# OSSI-1_COMMS_1.net
KiCad netlist of a schematic drawn in Altium Designer
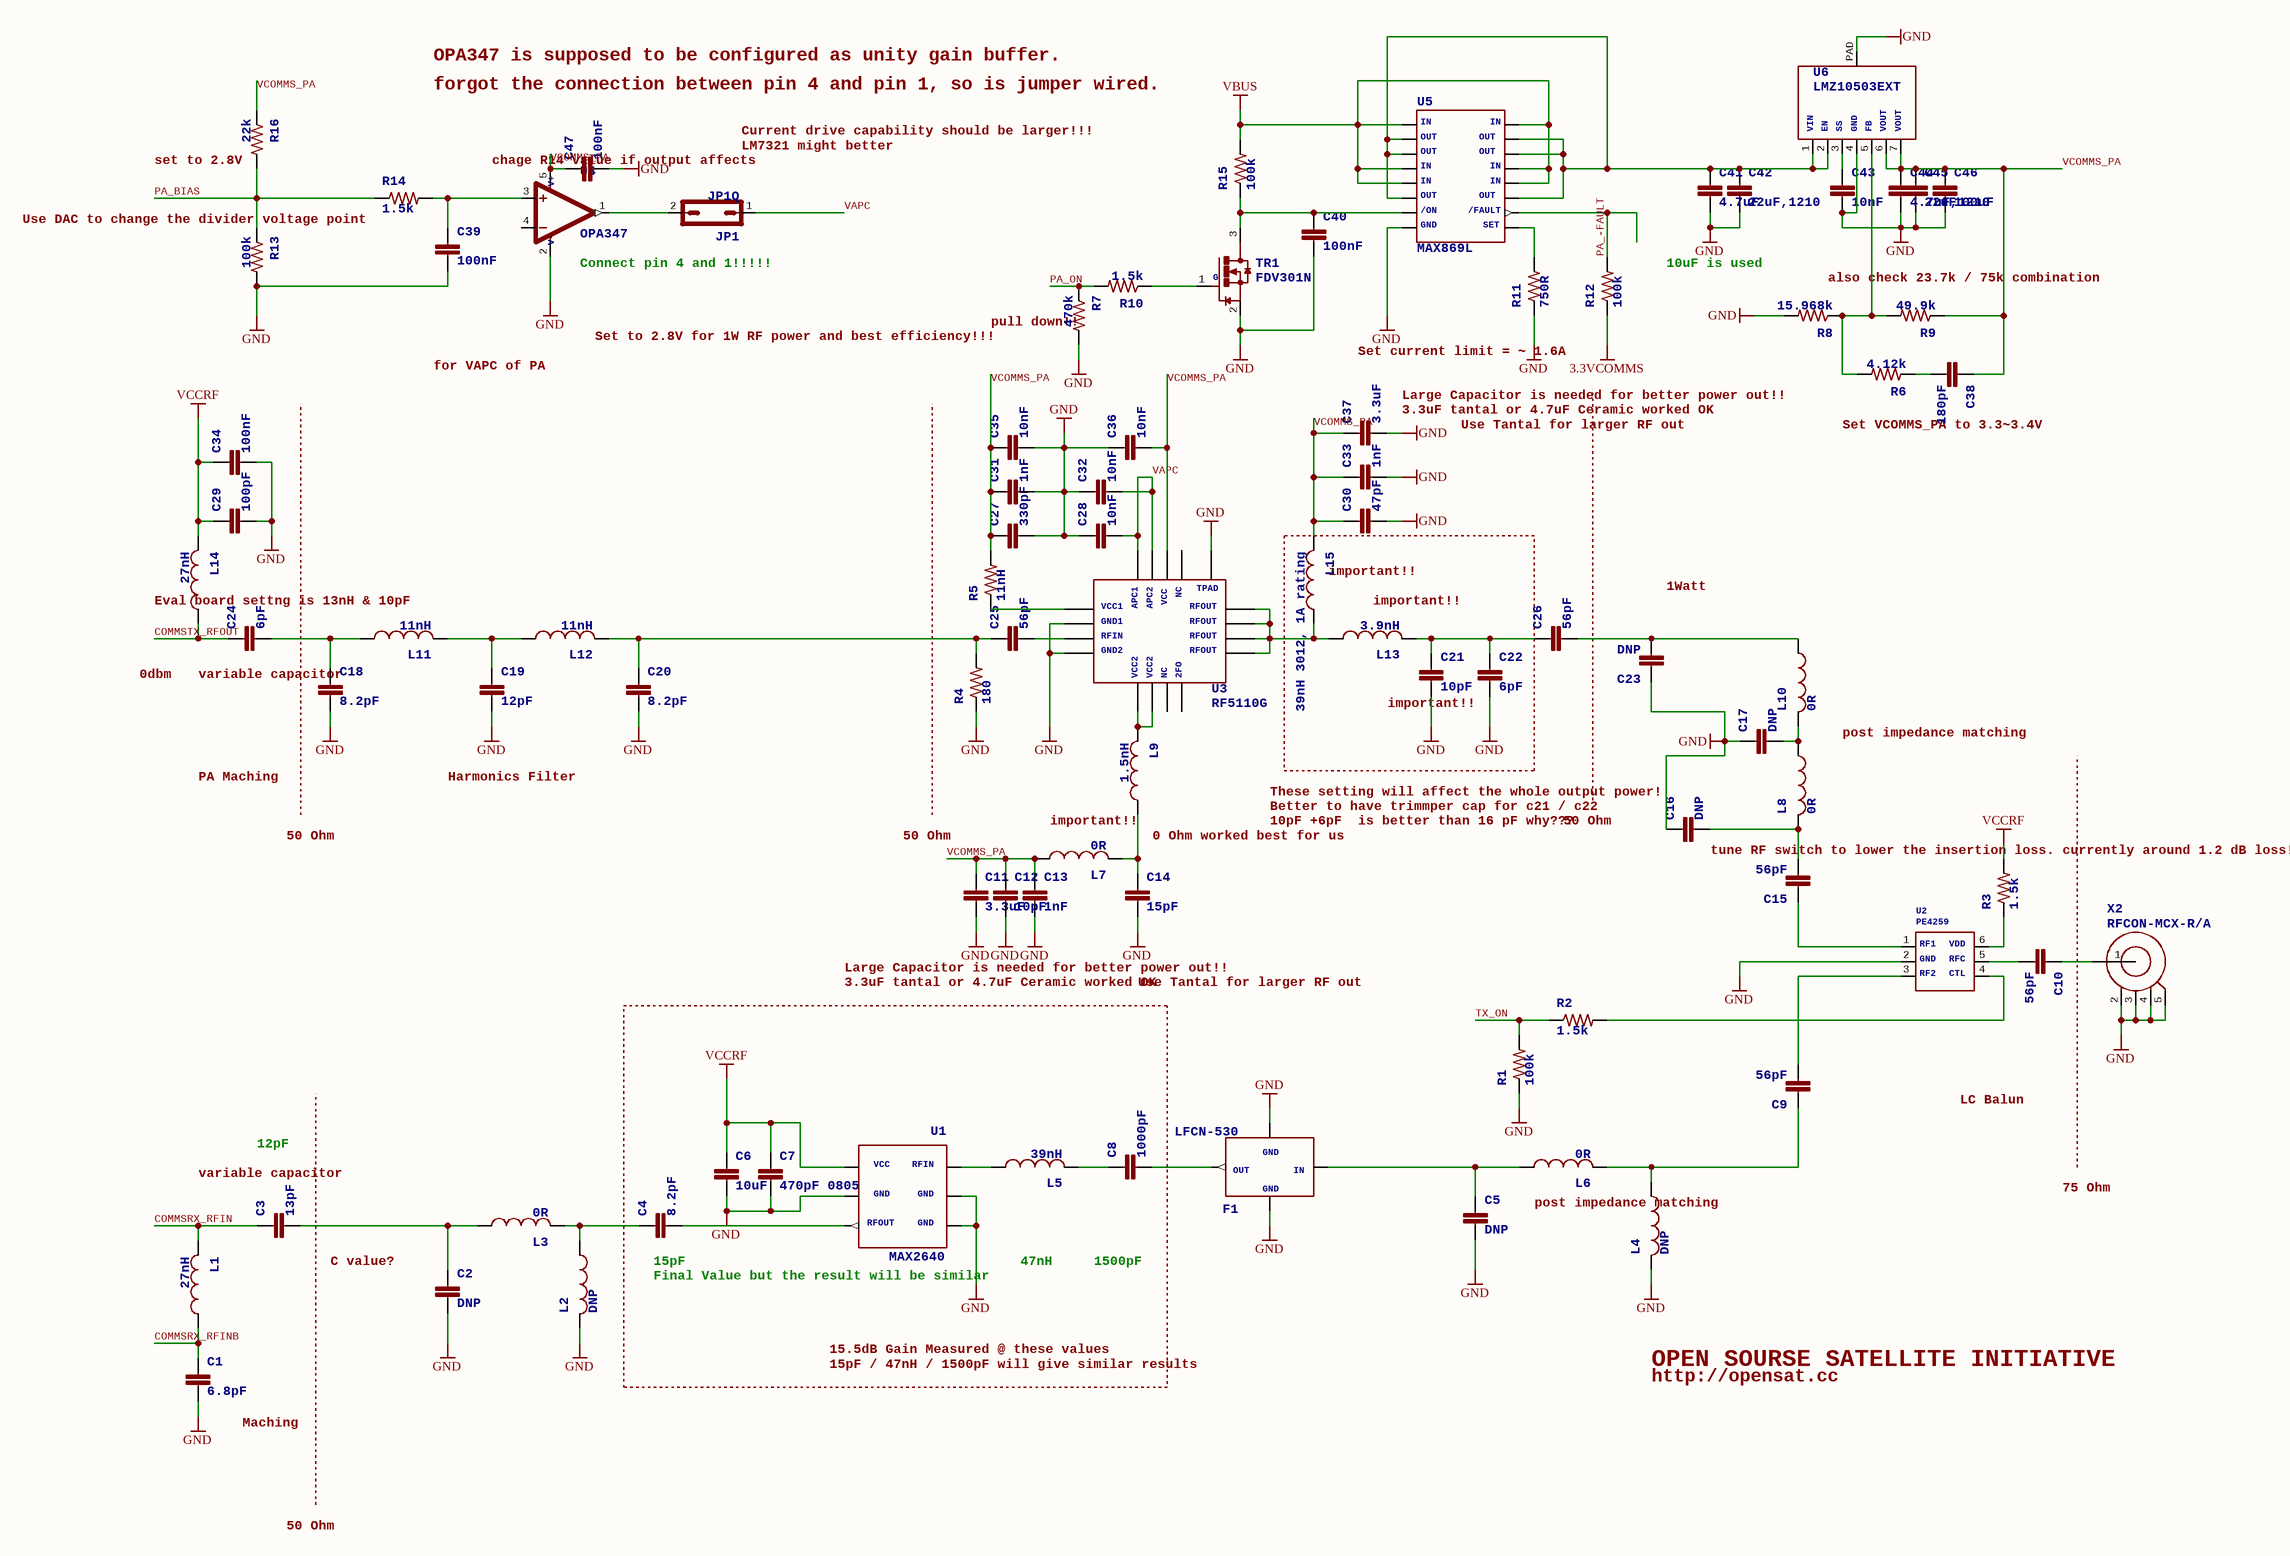
[diagram p0: OSSI-1 COMMS_1.SchDoc]

(export (version "E")
  (design (tool "Eeschema 10.0.6"))
  (components
    (comp (ref "C1")
      (value "6.8pF")
      (footprint "C0603(1608)")
      (fields (field (name ">NAME") "C1") (field (name ">VALUE") "6.8pF"))
      (libsource (lib "OSSI") (part "C0603(1608)"))
    )
    (comp (ref "C2")
      (value "DNP")
      (footprint "C0603(1608)")
      (fields (field (name ">NAME") "C2") (field (name ">VALUE") "DNP"))
      (libsource (lib "OSSI") (part "C0603(1608)"))
    )
    (comp (ref "C3")
      (value "13pF")
      (footprint "C0603(1608)")
      (fields (field (name ">NAME") "C3") (field (name ">VALUE") "13pF"))
      (libsource (lib "") (part "C0603(1608)_1"))
    )
    (comp (ref "C4")
      (value "8.2pF")
      (footprint "C0603(1608)")
      (fields (field (name ">NAME") "C4") (field (name ">VALUE") "8.2pF"))
      (libsource (lib "") (part "C0603(1608)_1"))
    )
    (comp (ref "C5")
      (value "DNP")
      (footprint "C0603(1608)")
      (fields (field (name ">NAME") "C5") (field (name ">VALUE") "DNP"))
      (libsource (lib "OSSI") (part "C0603(1608)"))
    )
    (comp (ref "C6")
      (value "10uF")
      (footprint "C1206-GCM31")
      (fields (field (name ">NAME") "C6") (field (name ">VALUE") "10uF"))
      (libsource (lib "OSSI") (part "C1206(3216)-GCM31"))
    )
    (comp (ref "C7")
      (value "470pF 0805")
      (footprint "C0805(2012)")
      (fields (field (name ">NAME") "C7") (field (name ">VALUE") "470pF 0805"))
      (libsource (lib "OSSI") (part "C0805(2012)"))
    )
    (comp (ref "C8")
      (value "1000pF")
      (footprint "C0603(1608)")
      (fields (field (name ">NAME") "C8") (field (name ">VALUE") "1000pF"))
      (libsource (lib "") (part "C0603(1608)_1"))
    )
    (comp (ref "C9")
      (value "56pF")
      (footprint "C0603(1608)")
      (fields (field (name ">NAME") "C9") (field (name ">VALUE") "56pF"))
      (libsource (lib "") (part "C0603(1608)_2"))
    )
    (comp (ref "C10")
      (value "56pF")
      (footprint "C0603(1608)")
      (fields (field (name ">NAME") "C10") (field (name ">VALUE") "56pF"))
      (libsource (lib "") (part "C0603(1608)_3"))
    )
    (comp (ref "C11")
      (value "3.3uF")
      (footprint "C1210-TMK325")
      (fields (field (name ">NAME") "C11") (field (name ">VALUE") "3.3uF"))
      (libsource (lib "OSSI") (part "C1210(3225)-TMK325"))
    )
    (comp (ref "C12")
      (value "10pF")
      (footprint "C0603(1608)")
      (fields (field (name ">NAME") "C12") (field (name ">VALUE") "10pF"))
      (libsource (lib "OSSI") (part "C0603(1608)"))
    )
    (comp (ref "C13")
      (value "1nF")
      (footprint "C0603(1608)")
      (fields (field (name ">NAME") "C13") (field (name ">VALUE") "1nF"))
      (libsource (lib "OSSI") (part "C0603(1608)"))
    )
    (comp (ref "C14")
      (value "15pF")
      (footprint "C0603(1608)")
      (fields (field (name ">NAME") "C14") (field (name ">VALUE") "15pF"))
      (libsource (lib "OSSI") (part "C0603(1608)"))
    )
    (comp (ref "C15")
      (value "56pF")
      (footprint "C0603(1608)")
      (fields (field (name ">NAME") "C15") (field (name ">VALUE") "56pF"))
      (libsource (lib "") (part "C0603(1608)_2"))
    )
    (comp (ref "C16")
      (value "DNP")
      (footprint "C0603(1608)")
      (fields (field (name ">NAME") "C16") (field (name ">VALUE") "DNP"))
      (libsource (lib "") (part "C0603(1608)_1"))
    )
    (comp (ref "C17")
      (value "DNP")
      (footprint "C0603(1608)")
      (fields (field (name ">NAME") "C17") (field (name ">VALUE") "DNP"))
      (libsource (lib "") (part "C0603(1608)_1"))
    )
    (comp (ref "C18")
      (value "8.2pF")
      (footprint "C0603(1608)")
      (fields (field (name ">NAME") "C18") (field (name ">VALUE") "8.2pF"))
      (libsource (lib "OSSI") (part "C0603(1608)"))
    )
    (comp (ref "C19")
      (value "12pF")
      (footprint "C0603(1608)")
      (fields (field (name ">NAME") "C19") (field (name ">VALUE") "12pF"))
      (libsource (lib "OSSI") (part "C0603(1608)"))
    )
    (comp (ref "C20")
      (value "8.2pF")
      (footprint "C0603(1608)")
      (fields (field (name ">NAME") "C20") (field (name ">VALUE") "8.2pF"))
      (libsource (lib "OSSI") (part "C0603(1608)"))
    )
    (comp (ref "C21")
      (value "10pF")
      (footprint "C0603(1608)")
      (fields (field (name ">NAME") "C21") (field (name ">VALUE") "10pF"))
      (libsource (lib "OSSI") (part "C0603(1608)"))
    )
    (comp (ref "C22")
      (value "6pF")
      (footprint "C0603(1608)")
      (fields (field (name ">NAME") "C22") (field (name ">VALUE") "6pF"))
      (libsource (lib "OSSI") (part "C0603(1608)"))
    )
    (comp (ref "C23")
      (value "DNP")
      (footprint "C0603(1608)")
      (fields (field (name ">NAME") "C23") (field (name ">VALUE") "DNP"))
      (libsource (lib "") (part "C0603(1608)_2"))
    )
    (comp (ref "C24")
      (value "6pF")
      (footprint "C0603(1608)")
      (fields (field (name ">NAME") "C24") (field (name ">VALUE") "6pF"))
      (libsource (lib "") (part "C0603(1608)_1"))
    )
    (comp (ref "C25")
      (value "56pF")
      (footprint "C0603(1608)")
      (fields (field (name ">NAME") "C25") (field (name ">VALUE") "56pF"))
      (libsource (lib "") (part "C0603(1608)_1"))
    )
    (comp (ref "C26")
      (value "56pF")
      (footprint "C0603(1608)")
      (fields (field (name ">NAME") "C26") (field (name ">VALUE") "56pF"))
      (libsource (lib "") (part "C0603(1608)_1"))
    )
    (comp (ref "C27")
      (value "330pF")
      (footprint "C0603(1608)")
      (fields (field (name ">NAME") "C27") (field (name ">VALUE") "330pF"))
      (libsource (lib "") (part "C0603(1608)_1"))
    )
    (comp (ref "C28")
      (value "10nF")
      (footprint "C0603(1608)")
      (fields (field (name ">NAME") "C28") (field (name ">VALUE") "10nF"))
      (libsource (lib "") (part "C0603(1608)_1"))
    )
    (comp (ref "C29")
      (value "100pF")
      (footprint "C0603(1608)")
      (fields (field (name ">NAME") "C29") (field (name ">VALUE") "100pF"))
      (libsource (lib "") (part "C0603(1608)_1"))
    )
    (comp (ref "C30")
      (value "47pF")
      (footprint "C0603(1608)")
      (fields (field (name ">NAME") "C30") (field (name ">VALUE") "47pF"))
      (libsource (lib "") (part "C0603(1608)_1"))
    )
    (comp (ref "C31")
      (value "1nF")
      (footprint "C0603(1608)")
      (fields (field (name ">NAME") "C31") (field (name ">VALUE") "1nF"))
      (libsource (lib "") (part "C0603(1608)_1"))
    )
    (comp (ref "C32")
      (value "10nF")
      (footprint "C0603(1608)")
      (fields (field (name ">NAME") "C32") (field (name ">VALUE") "10nF"))
      (libsource (lib "") (part "C0603(1608)_1"))
    )
    (comp (ref "C33")
      (value "1nF")
      (footprint "C0603(1608)")
      (fields (field (name ">NAME") "C33") (field (name ">VALUE") "1nF"))
      (libsource (lib "") (part "C0603(1608)_1"))
    )
    (comp (ref "C34")
      (value "100nF")
      (footprint "C0603(1608)")
      (fields (field (name ">NAME") "C34") (field (name ">VALUE") "100nF"))
      (libsource (lib "") (part "C0603(1608)_1"))
    )
    (comp (ref "C35")
      (value "10nF")
      (footprint "C0603(1608)")
      (fields (field (name ">NAME") "C35") (field (name ">VALUE") "10nF"))
      (libsource (lib "") (part "C0603(1608)_1"))
    )
    (comp (ref "C36")
      (value "10nF")
      (footprint "C0603(1608)")
      (fields (field (name ">NAME") "C36") (field (name ">VALUE") "10nF"))
      (libsource (lib "") (part "C0603(1608)_1"))
    )
    (comp (ref "C37")
      (value "3.3uF")
      (footprint "C1210-TMK325")
      (fields (field (name ">NAME") "C37") (field (name ">VALUE") "3.3uF"))
      (libsource (lib "") (part "C1210(3225)-TMK325_1"))
    )
    (comp (ref "C38")
      (value "180pF")
      (footprint "C0603(1608)")
      (fields (field (name ">NAME") "C38") (field (name ">VALUE") "180pF"))
      (libsource (lib "") (part "C0603(1608)_3"))
    )
    (comp (ref "C39")
      (value "100nF")
      (footprint "C0603(1608)")
      (fields (field (name ">NAME") "C39") (field (name ">VALUE") "100nF"))
      (libsource (lib "OSSI") (part "C0603(1608)"))
    )
    (comp (ref "C40")
      (value "100nF")
      (footprint "C0603(1608)")
      (fields (field (name ">NAME") "C40") (field (name ">VALUE") "100nF"))
      (libsource (lib "OSSI") (part "C0603(1608)"))
    )
    (comp (ref "C41")
      (value "4.7uF")
      (footprint "C1210-GCM32")
      (fields (field (name ">NAME") "C41") (field (name ">VALUE") "4.7uF"))
      (libsource (lib "OSSI") (part "C1210(3225)-GCM32"))
    )
    (comp (ref "C42")
      (value "22uF,1210")
      (footprint "C1210-GCM32")
      (fields (field (name ">NAME") "C42") (field (name ">VALUE") "22uF,1210"))
      (libsource (lib "OSSI") (part "C1210(3225)-GCM32"))
    )
    (comp (ref "C43")
      (value "10nF")
      (footprint "C0603(1608)")
      (fields (field (name ">NAME") "C43") (field (name ">VALUE") "10nF"))
      (libsource (lib "OSSI") (part "C0603(1608)"))
    )
    (comp (ref "C44")
      (value "4.7uF,1210")
      (footprint "C0805(2012)")
      (fields (field (name ">NAME") "C44") (field (name ">VALUE") "4.7uF,1210"))
      (libsource (lib "OSSI") (part "C0805(2012)"))
    )
    (comp (ref "C45")
      (value "22uF")
      (footprint "C1210-GCM32")
      (fields (field (name ">NAME") "C45") (field (name ">VALUE") "22uF"))
      (libsource (lib "OSSI") (part "C1210(3225)-GCM32"))
    )
    (comp (ref "C46")
      (value "100uF")
      (footprint "C1210-GCM32")
      (fields (field (name ">NAME") "C46") (field (name ">VALUE") "100uF"))
      (libsource (lib "OSSI") (part "C1210(3225)-GCM32"))
    )
    (comp (ref "C47")
      (value "100nF")
      (footprint "C0603(1608)")
      (fields (field (name ">NAME") "C47") (field (name ">VALUE") "100nF"))
      (libsource (lib "") (part "C0603(1608)_1"))
    )
    (comp (ref "F1")
      (value "LFCN-530")
      (footprint "LFCN")
      (fields
        (field (name "IN") "IN")
        (field (name "OUT") "OUT")
        (field (name "GND") "GND")
        (field (name "GND_1") "GND")
        (field (name ">NAME") "F1")
        (field (name ">VALUE") "LFCN-530")
      )
      (libsource (lib "OSSI") (part "LFCN-160"))
    )
    (comp (ref "JP1")
      (value "JP1Q")
      (footprint "JP1")
      (description "<b>JUMPER</b>")
      (fields (field (name ">NAME") "JP1") (field (name ">VALUE") "JP1Q"))
      (libsource (lib "OSSI") (part "JP1Q"))
    )
    (comp (ref "L1")
      (value "27nH")
      (footprint "L0603(1608)")
      (fields (field (name ">NAME") "L1") (field (name ">VALUE") "27nH"))
      (libsource (lib "OSSI") (part "L0603(1608)"))
    )
    (comp (ref "L2")
      (value "DNP")
      (footprint "L0603(1608)")
      (fields (field (name ">NAME") "L2") (field (name ">VALUE") "DNP"))
      (libsource (lib "OSSI") (part "L0603(1608)"))
    )
    (comp (ref "L3")
      (value "0R")
      (footprint "L0603(1608)")
      (fields (field (name ">NAME") "L3") (field (name ">VALUE") "0R"))
      (libsource (lib "OSSI") (part "L0603(1608)"))
    )
    (comp (ref "L4")
      (value "DNP")
      (footprint "L0603(1608)")
      (fields (field (name ">NAME") "L4") (field (name ">VALUE") "DNP"))
      (libsource (lib "OSSI") (part "L0603(1608)"))
    )
    (comp (ref "L5")
      (value "39nH")
      (footprint "L0603(1608)")
      (fields (field (name ">NAME") "L5") (field (name ">VALUE") "39nH"))
      (libsource (lib "OSSI") (part "L0603(1608)"))
    )
    (comp (ref "L6")
      (value "0R")
      (footprint "L0603(1608)")
      (fields (field (name ">NAME") "L6") (field (name ">VALUE") "0R"))
      (libsource (lib "OSSI") (part "L0603(1608)"))
    )
    (comp (ref "L7")
      (value "0R")
      (footprint "LQH32CN331K23L")
      (fields (field (name ">NAME") "L7") (field (name ">VALUE") "0R"))
      (libsource (lib "OSSI") (part "LLQH32CN"))
    )
    (comp (ref "L8")
      (value "0R")
      (footprint "L0603(1608)")
      (fields (field (name ">NAME") "L8") (field (name ">VALUE") "0R"))
      (libsource (lib "OSSI") (part "L0603(1608)"))
    )
    (comp (ref "L9")
      (value "1.5nH")
      (footprint "L0603(1608)")
      (fields (field (name ">NAME") "L9") (field (name ">VALUE") "1.5nH"))
      (libsource (lib "OSSI") (part "L0603(1608)"))
    )
    (comp (ref "L10")
      (value "0R")
      (footprint "L0603(1608)")
      (fields (field (name ">NAME") "L10") (field (name ">VALUE") "0R"))
      (libsource (lib "OSSI") (part "L0603(1608)"))
    )
    (comp (ref "L11")
      (value "11nH")
      (footprint "L0603(1608)")
      (fields (field (name ">NAME") "L11") (field (name ">VALUE") "11nH"))
      (libsource (lib "OSSI") (part "L0603(1608)"))
    )
    (comp (ref "L12")
      (value "11nH")
      (footprint "L0603(1608)")
      (fields (field (name ">NAME") "L12") (field (name ">VALUE") "11nH"))
      (libsource (lib "OSSI") (part "L0603(1608)"))
    )
    (comp (ref "L13")
      (value "3.9nH")
      (footprint "L0603(1608)")
      (fields (field (name ">NAME") "L13") (field (name ">VALUE") "3.9nH"))
      (libsource (lib "OSSI") (part "L0603(1608)"))
    )
    (comp (ref "L14")
      (value "27nH")
      (footprint "L0603(1608)")
      (fields (field (name ">NAME") "L14") (field (name ">VALUE") "27nH"))
      (libsource (lib "OSSI") (part "L0603(1608)"))
    )
    (comp (ref "L15")
      (value "39nH 3012, 1A rating")
      (footprint "NR3012")
      (fields (field (name ">NAME") "L15") (field (name ">VALUE") "39nH 3012, 1A rating"))
      (libsource (lib "OSSI") (part "LNR3012"))
    )
    (comp (ref "R1")
      (value "100k")
      (footprint "R0603(1608)")
      (fields (field (name ">NAME") "R1") (field (name ">VALUE") "100k"))
      (libsource (lib "OSSI") (part "R0603(1608)"))
    )
    (comp (ref "R2")
      (value "1.5k")
      (footprint "R0603(1608)")
      (fields (field (name ">NAME") "R2") (field (name ">VALUE") "1.5k"))
      (libsource (lib "OSSI") (part "R0603(1608)"))
    )
    (comp (ref "R3")
      (value "1.5k")
      (footprint "R0603(1608)")
      (fields (field (name ">NAME") "R3") (field (name ">VALUE") "1.5k"))
      (libsource (lib "OSSI") (part "R0603(1608)"))
    )
    (comp (ref "R4")
      (value "180")
      (footprint "R0603(1608)")
      (fields (field (name ">NAME") "R4") (field (name ">VALUE") "180"))
      (libsource (lib "OSSI") (part "R0603(1608)"))
    )
    (comp (ref "R5")
      (value "11nH")
      (footprint "R0603(1608)")
      (fields (field (name ">NAME") "R5") (field (name ">VALUE") "11nH"))
      (libsource (lib "OSSI") (part "R0603(1608)"))
    )
    (comp (ref "R6")
      (value "4.12k")
      (footprint "R0603(1608)")
      (fields (field (name ">NAME") "R6") (field (name ">VALUE") "4.12k"))
      (libsource (lib "OSSI") (part "R0603(1608)"))
    )
    (comp (ref "R7")
      (value "470k")
      (footprint "R0603(1608)")
      (fields (field (name ">NAME") "R7") (field (name ">VALUE") "470k"))
      (libsource (lib "OSSI") (part "R0603(1608)"))
    )
    (comp (ref "R8")
      (value "15.968k")
      (footprint "R0603(1608)")
      (fields (field (name ">NAME") "R8") (field (name ">VALUE") "15.968k"))
      (libsource (lib "OSSI") (part "R0603(1608)"))
    )
    (comp (ref "R9")
      (value "49.9k")
      (footprint "R0603(1608)")
      (fields (field (name ">NAME") "R9") (field (name ">VALUE") "49.9k"))
      (libsource (lib "OSSI") (part "R0603(1608)"))
    )
    (comp (ref "R10")
      (value "1.5k")
      (footprint "R0603(1608)")
      (fields (field (name ">NAME") "R10") (field (name ">VALUE") "1.5k"))
      (libsource (lib "OSSI") (part "R0603(1608)"))
    )
    (comp (ref "R11")
      (value "750R")
      (footprint "R0603(1608)")
      (fields (field (name ">NAME") "R11") (field (name ">VALUE") "750R"))
      (libsource (lib "OSSI") (part "R0603(1608)"))
    )
    (comp (ref "R12")
      (value "100k")
      (footprint "R0603(1608)")
      (fields (field (name ">NAME") "R12") (field (name ">VALUE") "100k"))
      (libsource (lib "OSSI") (part "R0603(1608)"))
    )
    (comp (ref "R13")
      (value "100k")
      (footprint "R0603(1608)")
      (fields (field (name ">NAME") "R13") (field (name ">VALUE") "100k"))
      (libsource (lib "OSSI") (part "R0603(1608)"))
    )
    (comp (ref "R14")
      (value "1.5k")
      (footprint "R0603(1608)")
      (fields (field (name ">NAME") "R14") (field (name ">VALUE") "1.5k"))
      (libsource (lib "OSSI") (part "R0603(1608)"))
    )
    (comp (ref "R15")
      (value "100k")
      (footprint "R0603(1608)")
      (fields (field (name ">NAME") "R15") (field (name ">VALUE") "100k"))
      (libsource (lib "OSSI") (part "R0603(1608)"))
    )
    (comp (ref "R16")
      (value "22k")
      (footprint "R0603(1608)")
      (fields (field (name ">NAME") "R16") (field (name ">VALUE") "22k"))
      (libsource (lib "OSSI") (part "R0603(1608)"))
    )
    (comp (ref "TR1")
      (value "FDV301N")
      (footprint "SOT23")
      (description "FDV301N Digital N channel - FET / Rdson = 5 Ohm / Vgs = 0.7~1.06V / Ids = 220mA")
      (fields (field (name "G") "G") (field (name ">NAME") "TR1") (field (name ">VALUE") "FDV301N"))
      (libsource (lib "OSSI") (part "FDV301N"))
    )
    (comp (ref "U1")
      (value "MAX2640")
      (footprint "SOT23-6")
      (fields
        (field (name ">NAME") "U1")
        (field (name "RFIN") "RFIN")
        (field (name "GND") "GND")
        (field (name "GND_1") "GND")
        (field (name "RFOUT") "RFOUT")
        (field (name "GND_2") "GND")
        (field (name "VCC") "VCC")
        (field (name ">VALUE") "MAX2640")
      )
      (libsource (lib "OSSI") (part "MAX2640"))
    )
    (comp (ref "U2")
      (value "PE4259")
      (footprint "SC70-6")
      (fields
        (field (name "RF1") "RF1")
        (field (name "GND") "GND")
        (field (name "RF2") "RF2")
        (field (name "CTL") "CTL")
        (field (name "RFC") "RFC")
        (field (name "VDD") "VDD")
        (field (name ">NAME") "U2")
        (field (name ">VALUE") "PE4259")
      )
      (libsource (lib "OSSI") (part "PE4259"))
    )
    (comp (ref "U3")
      (value "RF5110G")
      (footprint "RF5110G")
      (description "<b>RF5110G</b>\n<br />\n3V GSM RF Power Amplifirer\n<br />\n+36dBm Output Power at 3.5V")
      (fields
        (field (name "VCC1") "VCC1")
        (field (name "GND1") "GND1")
        (field (name "RFIN") "RFIN")
        (field (name "GND2") "GND2")
        (field (name "VCC2") "VCC2")
        (field (name "VCC2_1") "VCC2")
        (field (name "NC") "NC")
        (field (name "2FO") "2FO")
        (field (name "RFOUT") "RFOUT")
        (field (name "RFOUT_1") "RFOUT")
        (field (name "RFOUT_2") "RFOUT")
        (field (name "RFOUT_3") "RFOUT")
        (field (name "NC_1") "NC")
        (field (name "VCC") "VCC")
        (field (name "APC2") "APC2")
        (field (name "APC1") "APC1")
        (field (name ">NAME") "U3")
        (field (name ">VALUE") "RF5110G")
        (field (name "TPAD") "TPAD")
      )
      (libsource (lib "OSSI") (part "RF5110G"))
    )
    (comp (ref "U4")
      (value "OPA347")
      (footprint "SOT23-5DBV")
      (fields
        (field (name ">NAME") "U4")
        (field (name ">VALUE") "OPA347")
        (field (name "V+") "V+")
        (field (name "V-") "V-")
      )
      (libsource (lib "OSSI") (part "OPA347"))
    )
    (comp (ref "U5")
      (value "MAX869L")
      (footprint "16QSOP")
      (description "2A, Current-Limited, High-Side\nP-Channel Switch with Thermal Shutdown")
      (fields
        (field (name "IN") "IN")
        (field (name "OUT") "OUT")
        (field (name "OUT_1") "OUT")
        (field (name "IN_1") "IN")
        (field (name "IN_2") "IN")
        (field (name "IN_3") "IN")
        (field (name "IN_4") "IN")
        (field (name "IN_5") "IN")
        (field (name "OUT_2") "OUT")
        (field (name "GND") "GND")
        (field (name "OUT_3") "OUT")
        (field (name "OUT_4") "OUT")
        (field (name "OUT_5") "OUT")
        (field (name "/ON") "/ON")
        (field (name "/FAULT") "/FAULT")
        (field (name "SET") "SET")
        (field (name ">NAME") "U5")
        (field (name ">VALUE") "MAX869L")
      )
      (libsource (lib "OSSI") (part "MAX869L"))
    )
    (comp (ref "U6")
      (value "LMZ10503EXT")
      (footprint "TO-PMOD-7")
      (fields
        (field (name "VIN") "VIN")
        (field (name "EN") "EN")
        (field (name "SS") "SS")
        (field (name "GND") "GND")
        (field (name "FB") "FB")
        (field (name "VOUT") "VOUT")
        (field (name "VOUT_1") "VOUT")
        (field (name ">NAME") "U6")
        (field (name ">VALUE") "LMZ10503EXT")
      )
      (libsource (lib "OSSI") (part "LMZ10503EXT"))
    )
    (comp (ref "X2")
      (value "RFCON-MCX-R/A")
      (footprint "MCX-R/A")
      (description "RF Connectors")
      (fields (field (name ">NAME") "X2") (field (name ">VALUE") "RFCON-MCX-R/A"))
      (libsource (lib "OSSI") (part "RFCON-MCX-R/A"))
    )
  )
  (nets
    (net (code "1") (name "/COMMSRX_RFIN") (class "Default")
      (node (ref "C3") (pin "1") (pinfunction "1_1") (pintype "passive"))
      (node (ref "L1") (pin "2") (pinfunction "2_2") (pintype "passive"))
    )
    (net (code "2") (name "/COMMSRX_RFINB") (class "Default")
      (node (ref "C1") (pin "1") (pinfunction "1_1") (pintype "passive"))
      (node (ref "L1") (pin "1") (pinfunction "1_1") (pintype "passive"))
    )
    (net (code "3") (name "/COMMSTX_RFOUT") (class "Default")
      (node (ref "C24") (pin "1") (pinfunction "1_1") (pintype "passive"))
      (node (ref "L14") (pin "1") (pinfunction "1_1") (pintype "passive"))
    )
    (net (code "4") (name "/PA_-FAULT") (class "Default")
      (node (ref "R12") (pin "2") (pinfunction "2_2") (pintype "passive"))
      (node (ref "U5") (pin "10") (pinfunction "P$10_10") (pintype "output"))
    )
    (net (code "5") (name "/PA_BIAS") (class "Default")
      (node (ref "R13") (pin "1") (pinfunction "1_1") (pintype "passive"))
      (node (ref "R14") (pin "1") (pinfunction "1_1") (pintype "passive"))
      (node (ref "R16") (pin "2") (pinfunction "2_2") (pintype "passive"))
    )
    (net (code "6") (name "/PA_ON") (class "Default")
      (node (ref "R10") (pin "2") (pinfunction "2_2") (pintype "passive"))
      (node (ref "R7") (pin "1") (pinfunction "1_1") (pintype "passive"))
    )
    (net (code "7") (name "/TX_ON") (class "Default")
      (node (ref "R1") (pin "2") (pinfunction "2_2") (pintype "passive"))
      (node (ref "R2") (pin "1") (pinfunction "1_1") (pintype "passive"))
    )
    (net (code "8") (name "/VAPC") (class "Default")
      (node (ref "C28") (pin "2") (pinfunction "2_2") (pintype "passive"))
      (node (ref "C32") (pin "2") (pinfunction "2_2") (pintype "passive"))
      (node (ref "JP1") (pin "1") (pinfunction "1_1") (pintype "passive"))
      (node (ref "U3") (pin "15") (pinfunction "P$15_15") (pintype "passive"))
      (node (ref "U3") (pin "16") (pinfunction "P$16_16") (pintype "passive"))
    )
    (net (code "9") (name "/VCOMMS_PA") (class "Default")
      (node (ref "C11") (pin "P$1") (pinfunction "1_P$1") (pintype "passive"))
      (node (ref "C12") (pin "1") (pinfunction "1_1") (pintype "passive"))
      (node (ref "C13") (pin "1") (pinfunction "1_1") (pintype "passive"))
      (node (ref "C27") (pin "1") (pinfunction "1_1") (pintype "passive"))
      (node (ref "C30") (pin "1") (pinfunction "1_1") (pintype "passive"))
      (node (ref "C31") (pin "1") (pinfunction "1_1") (pintype "passive"))
      (node (ref "C33") (pin "1") (pinfunction "1_1") (pintype "passive"))
      (node (ref "C35") (pin "1") (pinfunction "1_1") (pintype "passive"))
      (node (ref "C36") (pin "2") (pinfunction "2_2") (pintype "passive"))
      (node (ref "C37") (pin "P$1") (pinfunction "1_P$1") (pintype "passive"))
      (node (ref "C38") (pin "1") (pinfunction "1_1") (pintype "passive"))
      (node (ref "C44") (pin "1") (pinfunction "1_1") (pintype "passive"))
      (node (ref "C45") (pin "P$1") (pinfunction "1_P$1") (pintype "passive"))
      (node (ref "C46") (pin "P$1") (pinfunction "1_P$1") (pintype "passive"))
      (node (ref "C47") (pin "1") (pinfunction "1_1") (pintype "passive"))
      (node (ref "L15") (pin "P$2") (pinfunction "2_P$2") (pintype "passive"))
      (node (ref "L7") (pin "P$1") (pinfunction "1_P$1") (pintype "passive"))
      (node (ref "R16") (pin "1") (pinfunction "1_1") (pintype "passive"))
      (node (ref "R5") (pin "2") (pinfunction "2_2") (pintype "passive"))
      (node (ref "R9") (pin "1") (pinfunction "1_1") (pintype "passive"))
      (node (ref "U3") (pin "14") (pinfunction "P$14_14") (pintype "passive"))
      (node (ref "U4") (pin "5") (pinfunction "V+_5") (pintype "power_in"))
      (node (ref "U6") (pin "6") (pinfunction "P$6_6") (pintype "power_in"))
      (node (ref "U6") (pin "7") (pinfunction "P$7_7") (pintype "power_in"))
    )
    (net (code "10") (name "3.3VCOMMS") (class "Default")
      (node (ref "R12") (pin "1") (pinfunction "1_1") (pintype "passive"))
    )
    (net (code "11") (name "GND") (class "Default")
      (node (ref "C1") (pin "2") (pinfunction "2_2") (pintype "passive"))
      (node (ref "C11") (pin "P$2") (pinfunction "2_P$2") (pintype "passive"))
      (node (ref "C12") (pin "2") (pinfunction "2_2") (pintype "passive"))
      (node (ref "C13") (pin "2") (pinfunction "2_2") (pintype "passive"))
      (node (ref "C14") (pin "2") (pinfunction "2_2") (pintype "passive"))
      (node (ref "C16") (pin "1") (pinfunction "1_1") (pintype "passive"))
      (node (ref "C17") (pin "1") (pinfunction "1_1") (pintype "passive"))
      (node (ref "C18") (pin "2") (pinfunction "2_2") (pintype "passive"))
      (node (ref "C19") (pin "2") (pinfunction "2_2") (pintype "passive"))
      (node (ref "C2") (pin "2") (pinfunction "2_2") (pintype "passive"))
      (node (ref "C20") (pin "2") (pinfunction "2_2") (pintype "passive"))
      (node (ref "C21") (pin "2") (pinfunction "2_2") (pintype "passive"))
      (node (ref "C22") (pin "2") (pinfunction "2_2") (pintype "passive"))
      (node (ref "C23") (pin "1") (pinfunction "1_1") (pintype "passive"))
      (node (ref "C27") (pin "2") (pinfunction "2_2") (pintype "passive"))
      (node (ref "C28") (pin "1") (pinfunction "1_1") (pintype "passive"))
      (node (ref "C29") (pin "2") (pinfunction "2_2") (pintype "passive"))
      (node (ref "C30") (pin "2") (pinfunction "2_2") (pintype "passive"))
      (node (ref "C31") (pin "2") (pinfunction "2_2") (pintype "passive"))
      (node (ref "C32") (pin "1") (pinfunction "1_1") (pintype "passive"))
      (node (ref "C33") (pin "2") (pinfunction "2_2") (pintype "passive"))
      (node (ref "C34") (pin "2") (pinfunction "2_2") (pintype "passive"))
      (node (ref "C35") (pin "2") (pinfunction "2_2") (pintype "passive"))
      (node (ref "C36") (pin "1") (pinfunction "1_1") (pintype "passive"))
      (node (ref "C37") (pin "P$2") (pinfunction "2_P$2") (pintype "passive"))
      (node (ref "C39") (pin "2") (pinfunction "2_2") (pintype "passive"))
      (node (ref "C40") (pin "2") (pinfunction "2_2") (pintype "passive"))
      (node (ref "C41") (pin "P$2") (pinfunction "2_P$2") (pintype "passive"))
      (node (ref "C42") (pin "P$2") (pinfunction "2_P$2") (pintype "passive"))
      (node (ref "C43") (pin "2") (pinfunction "2_2") (pintype "passive"))
      (node (ref "C44") (pin "2") (pinfunction "2_2") (pintype "passive"))
      (node (ref "C45") (pin "P$2") (pinfunction "2_P$2") (pintype "passive"))
      (node (ref "C46") (pin "P$2") (pinfunction "2_P$2") (pintype "passive"))
      (node (ref "C47") (pin "2") (pinfunction "2_2") (pintype "passive"))
      (node (ref "C5") (pin "2") (pinfunction "2_2") (pintype "passive"))
      (node (ref "C6") (pin "P$2") (pinfunction "2_P$2") (pintype "passive"))
      (node (ref "C7") (pin "2") (pinfunction "2_2") (pintype "passive"))
      (node (ref "F1") (pin "2") (pinfunction "P$2_2") (pintype "power_in"))
      (node (ref "F1") (pin "4") (pinfunction "P$4_4") (pintype "power_in"))
      (node (ref "L2") (pin "2") (pinfunction "2_2") (pintype "passive"))
      (node (ref "L4") (pin "2") (pinfunction "2_2") (pintype "passive"))
      (node (ref "R1") (pin "1") (pinfunction "1_1") (pintype "passive"))
      (node (ref "R11") (pin "1") (pinfunction "1_1") (pintype "passive"))
      (node (ref "R13") (pin "2") (pinfunction "2_2") (pintype "passive"))
      (node (ref "R4") (pin "1") (pinfunction "1_1") (pintype "passive"))
      (node (ref "R7") (pin "2") (pinfunction "2_2") (pintype "passive"))
      (node (ref "R8") (pin "2") (pinfunction "2_2") (pintype "passive"))
      (node (ref "TR1") (pin "2") (pinfunction "S_2") (pintype "passive"))
      (node (ref "U1") (pin "2") (pinfunction "2_2") (pintype "power_in"))
      (node (ref "U1") (pin "3") (pinfunction "3_3") (pintype "power_in"))
      (node (ref "U1") (pin "5") (pinfunction "5_5") (pintype "power_in"))
      (node (ref "U2") (pin "2") (pinfunction "P$2_2") (pintype "passive"))
      (node (ref "U3") (pin "2") (pinfunction "P$2_2") (pintype "passive"))
      (node (ref "U3") (pin "4") (pinfunction "P$4_4") (pintype "passive"))
      (node (ref "U3") (pin "TPAD") (pinfunction "P$17_TPAD") (pintype "passive"))
      (node (ref "U4") (pin "2") (pinfunction "V-_2") (pintype "power_in"))
      (node (ref "U5") (pin "8") (pinfunction "P$8_8") (pintype "power_in"))
      (node (ref "U6") (pin "4") (pinfunction "P$4_4") (pintype "power_in"))
      (node (ref "U6") (pin "PAD") (pinfunction "P$8_PAD") (pintype "power_in"))
      (node (ref "X2") (pin "2") (pinfunction "2_2") (pintype "open_emitter"))
      (node (ref "X2") (pin "3") (pinfunction "3_3") (pintype "open_emitter"))
      (node (ref "X2") (pin "4") (pinfunction "4_4") (pintype "open_emitter"))
      (node (ref "X2") (pin "5") (pinfunction "5_5") (pintype "open_emitter"))
    )
    (net (code "12") (name "Net-(C2-Pad1)") (class "Default")
      (node (ref "C2") (pin "1") (pinfunction "1_1") (pintype "passive"))
      (node (ref "C3") (pin "2") (pinfunction "2_2") (pintype "passive"))
      (node (ref "L3") (pin "1") (pinfunction "1_1") (pintype "passive"))
    )
    (net (code "13") (name "Net-(C4-Pad1)") (class "Default")
      (node (ref "C4") (pin "1") (pinfunction "1_1") (pintype "passive"))
      (node (ref "L2") (pin "1") (pinfunction "1_1") (pintype "passive"))
      (node (ref "L3") (pin "2") (pinfunction "2_2") (pintype "passive"))
    )
    (net (code "14") (name "Net-(C4-Pad2)") (class "Default")
      (node (ref "C4") (pin "2") (pinfunction "2_2") (pintype "passive"))
      (node (ref "U1") (pin "4") (pinfunction "4_4") (pintype "output"))
    )
    (net (code "15") (name "Net-(C8-Pad1)") (class "Default")
      (node (ref "C8") (pin "1") (pinfunction "1_1") (pintype "passive"))
      (node (ref "L5") (pin "2") (pinfunction "2_2") (pintype "passive"))
    )
    (net (code "16") (name "Net-(C9-Pad1)") (class "Default")
      (node (ref "C9") (pin "1") (pinfunction "1_1") (pintype "passive"))
      (node (ref "L4") (pin "1") (pinfunction "1_1") (pintype "passive"))
      (node (ref "L6") (pin "2") (pinfunction "2_2") (pintype "passive"))
    )
    (net (code "17") (name "Net-(C10-Pad1)") (class "Default")
      (node (ref "C10") (pin "1") (pinfunction "1_1") (pintype "passive"))
      (node (ref "X2") (pin "1") (pinfunction "1_1") (pintype "passive"))
    )
    (net (code "18") (name "Net-(C15-Pad2)") (class "Default")
      (node (ref "C15") (pin "2") (pinfunction "2_2") (pintype "passive"))
      (node (ref "C16") (pin "2") (pinfunction "2_2") (pintype "passive"))
      (node (ref "L8") (pin "2") (pinfunction "2_2") (pintype "passive"))
    )
    (net (code "19") (name "Net-(C17-Pad2)") (class "Default")
      (node (ref "C17") (pin "2") (pinfunction "2_2") (pintype "passive"))
      (node (ref "L10") (pin "2") (pinfunction "2_2") (pintype "passive"))
      (node (ref "L8") (pin "1") (pinfunction "1_1") (pintype "passive"))
    )
    (net (code "20") (name "Net-(C18-Pad1)") (class "Default")
      (node (ref "C18") (pin "1") (pinfunction "1_1") (pintype "passive"))
      (node (ref "C24") (pin "2") (pinfunction "2_2") (pintype "passive"))
      (node (ref "L11") (pin "1") (pinfunction "1_1") (pintype "passive"))
    )
    (net (code "21") (name "Net-(C19-Pad1)") (class "Default")
      (node (ref "C19") (pin "1") (pinfunction "1_1") (pintype "passive"))
      (node (ref "L11") (pin "2") (pinfunction "2_2") (pintype "passive"))
      (node (ref "L12") (pin "1") (pinfunction "1_1") (pintype "passive"))
    )
    (net (code "22") (name "Net-(C20-Pad1)") (class "Default")
      (node (ref "C20") (pin "1") (pinfunction "1_1") (pintype "passive"))
      (node (ref "C25") (pin "1") (pinfunction "1_1") (pintype "passive"))
      (node (ref "L12") (pin "2") (pinfunction "2_2") (pintype "passive"))
      (node (ref "R4") (pin "2") (pinfunction "2_2") (pintype "passive"))
    )
    (net (code "23") (name "Net-(C21-Pad1)") (class "Default")
      (node (ref "C21") (pin "1") (pinfunction "1_1") (pintype "passive"))
      (node (ref "C22") (pin "1") (pinfunction "1_1") (pintype "passive"))
      (node (ref "C26") (pin "1") (pinfunction "1_1") (pintype "passive"))
      (node (ref "L13") (pin "2") (pinfunction "2_2") (pintype "passive"))
    )
    (net (code "24") (name "Net-(C23-Pad2)") (class "Default")
      (node (ref "C23") (pin "2") (pinfunction "2_2") (pintype "passive"))
      (node (ref "C26") (pin "2") (pinfunction "2_2") (pintype "passive"))
      (node (ref "L10") (pin "1") (pinfunction "1_1") (pintype "passive"))
    )
    (net (code "25") (name "Net-(C38-Pad2)") (class "Default")
      (node (ref "C38") (pin "2") (pinfunction "2_2") (pintype "passive"))
      (node (ref "R6") (pin "1") (pinfunction "1_1") (pintype "passive"))
    )
    (net (code "26") (name "Net-(C41-1)") (class "Default")
      (node (ref "C41") (pin "P$1") (pinfunction "1_P$1") (pintype "passive"))
      (node (ref "C42") (pin "P$1") (pinfunction "1_P$1") (pintype "passive"))
      (node (ref "U5") (pin "11") (pinfunction "P$11_11") (pintype "power_in"))
      (node (ref "U5") (pin "14") (pinfunction "P$14_14") (pintype "power_in"))
      (node (ref "U5") (pin "15") (pinfunction "P$15_15") (pintype "power_in"))
      (node (ref "U5") (pin "2") (pinfunction "P$2_2") (pintype "power_in"))
      (node (ref "U5") (pin "3") (pinfunction "P$3_3") (pintype "power_in"))
      (node (ref "U5") (pin "6") (pinfunction "P$6_6") (pintype "power_in"))
      (node (ref "U6") (pin "1") (pinfunction "P$1_1") (pintype "power_in"))
      (node (ref "U6") (pin "2") (pinfunction "P$2_2") (pintype "passive"))
    )
    (net (code "27") (name "Net-(F1-P$1)") (class "Default")
      (node (ref "C5") (pin "1") (pinfunction "1_1") (pintype "passive"))
      (node (ref "F1") (pin "1") (pinfunction "P$1_1") (pintype "passive"))
      (node (ref "L6") (pin "1") (pinfunction "1_1") (pintype "passive"))
    )
    (net (code "28") (name "Net-(F1-P$3)") (class "Default")
      (node (ref "C8") (pin "2") (pinfunction "2_2") (pintype "passive"))
      (node (ref "F1") (pin "3") (pinfunction "P$3_3") (pintype "output"))
    )
    (net (code "29") (name "Net-(L5-Pad1)") (class "Default")
      (node (ref "L5") (pin "1") (pinfunction "1_1") (pintype "passive"))
      (node (ref "U1") (pin "1") (pinfunction "1_1") (pintype "passive"))
    )
    (net (code "30") (name "Net-(L7-2)") (class "Default")
      (node (ref "C14") (pin "1") (pinfunction "1_1") (pintype "passive"))
      (node (ref "L7") (pin "P$2") (pinfunction "2_P$2") (pintype "passive"))
      (node (ref "L9") (pin "1") (pinfunction "1_1") (pintype "passive"))
    )
    (net (code "31") (name "Net-(L15-1)") (class "Default")
      (node (ref "L13") (pin "1") (pinfunction "1_1") (pintype "passive"))
      (node (ref "L15") (pin "P$1") (pinfunction "1_P$1") (pintype "passive"))
      (node (ref "U3") (pin "10") (pinfunction "P$10_10") (pintype "passive"))
      (node (ref "U3") (pin "11") (pinfunction "P$11_11") (pintype "passive"))
      (node (ref "U3") (pin "12") (pinfunction "P$12_12") (pintype "passive"))
      (node (ref "U3") (pin "9") (pinfunction "P$9_9") (pintype "passive"))
    )
    (net (code "32") (name "Net-(TR1-D)") (class "Default")
      (node (ref "C40") (pin "1") (pinfunction "1_1") (pintype "passive"))
      (node (ref "R15") (pin "1") (pinfunction "1_1") (pintype "passive"))
      (node (ref "TR1") (pin "3") (pinfunction "D_3") (pintype "passive"))
      (node (ref "U5") (pin "7") (pinfunction "P$7_7") (pintype "passive"))
    )
    (net (code "33") (name "Net-(TR1-G)") (class "Default")
      (node (ref "R10") (pin "1") (pinfunction "1_1") (pintype "passive"))
      (node (ref "TR1") (pin "1") (pinfunction "G_1") (pintype "passive"))
    )
    (net (code "34") (name "Net-(U2-P$1)") (class "Default")
      (node (ref "C15") (pin "1") (pinfunction "1_1") (pintype "passive"))
      (node (ref "U2") (pin "1") (pinfunction "P$1_1") (pintype "passive"))
    )
    (net (code "35") (name "Net-(U2-P$3)") (class "Default")
      (node (ref "C9") (pin "2") (pinfunction "2_2") (pintype "passive"))
      (node (ref "U2") (pin "3") (pinfunction "P$3_3") (pintype "passive"))
    )
    (net (code "36") (name "Net-(U2-P$4)") (class "Default")
      (node (ref "R2") (pin "2") (pinfunction "2_2") (pintype "passive"))
      (node (ref "U2") (pin "4") (pinfunction "P$4_4") (pintype "passive"))
    )
    (net (code "37") (name "Net-(U2-P$5)") (class "Default")
      (node (ref "C10") (pin "2") (pinfunction "2_2") (pintype "passive"))
      (node (ref "U2") (pin "5") (pinfunction "P$5_5") (pintype "passive"))
    )
    (net (code "38") (name "Net-(U2-P$6)") (class "Default")
      (node (ref "R3") (pin "1") (pinfunction "1_1") (pintype "passive"))
      (node (ref "U2") (pin "6") (pinfunction "P$6_6") (pintype "passive"))
    )
    (net (code "39") (name "Net-(U3-P$1)") (class "Default")
      (node (ref "R5") (pin "1") (pinfunction "1_1") (pintype "passive"))
      (node (ref "U3") (pin "1") (pinfunction "P$1_1") (pintype "passive"))
    )
    (net (code "40") (name "Net-(U3-P$3)") (class "Default")
      (node (ref "C25") (pin "2") (pinfunction "2_2") (pintype "passive"))
      (node (ref "U3") (pin "3") (pinfunction "P$3_3") (pintype "passive"))
    )
    (net (code "41") (name "Net-(U3-P$5)") (class "Default")
      (node (ref "L9") (pin "2") (pinfunction "2_2") (pintype "passive"))
      (node (ref "U3") (pin "5") (pinfunction "P$5_5") (pintype "passive"))
      (node (ref "U3") (pin "6") (pinfunction "P$6_6") (pintype "passive"))
    )
    (net (code "42") (name "Net-(U4-+IN)") (class "Default")
      (node (ref "C39") (pin "1") (pinfunction "1_1") (pintype "passive"))
      (node (ref "R14") (pin "2") (pinfunction "2_2") (pintype "passive"))
      (node (ref "U4") (pin "3") (pinfunction "+IN_3") (pintype "passive"))
    )
    (net (code "43") (name "Net-(U4-OUT)") (class "Default")
      (node (ref "JP1") (pin "2") (pinfunction "2_2") (pintype "passive"))
      (node (ref "U4") (pin "1") (pinfunction "OUT_1") (pintype "output"))
    )
    (net (code "44") (name "Net-(U5-P$9)") (class "Default")
      (node (ref "R11") (pin "2") (pinfunction "2_2") (pintype "passive"))
      (node (ref "U5") (pin "9") (pinfunction "P$9_9") (pintype "passive"))
    )
    (net (code "45") (name "Net-(U6-P$3)") (class "Default")
      (node (ref "C43") (pin "1") (pinfunction "1_1") (pintype "passive"))
      (node (ref "U6") (pin "3") (pinfunction "P$3_3") (pintype "passive"))
    )
    (net (code "46") (name "Net-(U6-P$5)") (class "Default")
      (node (ref "R6") (pin "2") (pinfunction "2_2") (pintype "passive"))
      (node (ref "R8") (pin "1") (pinfunction "1_1") (pintype "passive"))
      (node (ref "R9") (pin "2") (pinfunction "2_2") (pintype "passive"))
      (node (ref "U6") (pin "5") (pinfunction "P$5_5") (pintype "passive"))
    )
    (net (code "47") (name "VBUS") (class "Default")
      (node (ref "R15") (pin "2") (pinfunction "2_2") (pintype "passive"))
      (node (ref "U5") (pin "1") (pinfunction "P$1_1") (pintype "power_in"))
      (node (ref "U5") (pin "12") (pinfunction "P$12_12") (pintype "power_in"))
      (node (ref "U5") (pin "13") (pinfunction "P$13_13") (pintype "power_in"))
      (node (ref "U5") (pin "16") (pinfunction "P$16_16") (pintype "power_in"))
      (node (ref "U5") (pin "4") (pinfunction "P$4_4") (pintype "power_in"))
      (node (ref "U5") (pin "5") (pinfunction "P$5_5") (pintype "power_in"))
    )
    (net (code "48") (name "VCCRF") (class "Default")
      (node (ref "C29") (pin "1") (pinfunction "1_1") (pintype "passive"))
      (node (ref "C34") (pin "1") (pinfunction "1_1") (pintype "passive"))
      (node (ref "C6") (pin "P$1") (pinfunction "1_P$1") (pintype "passive"))
      (node (ref "C7") (pin "1") (pinfunction "1_1") (pintype "passive"))
      (node (ref "L14") (pin "2") (pinfunction "2_2") (pintype "passive"))
      (node (ref "R3") (pin "2") (pinfunction "2_2") (pintype "passive"))
      (node (ref "U1") (pin "6") (pinfunction "6_6") (pintype "power_in"))
    )
    (net (code "49") (name "unconnected-(U3-P$7-Pad7)") (class "Default")
      (node (ref "U3") (pin "7") (pinfunction "P$7_7") (pintype "passive"))
    )
    (net (code "50") (name "unconnected-(U3-P$8-Pad8)") (class "Default")
      (node (ref "U3") (pin "8") (pinfunction "P$8_8") (pintype "passive"))
    )
    (net (code "51") (name "unconnected-(U3-P$13-Pad13)") (class "Default")
      (node (ref "U3") (pin "13") (pinfunction "P$13_13") (pintype "passive"))
    )
    (net (code "52") (name "unconnected-(U4--IN-Pad4)") (class "Default")
      (node (ref "U4") (pin "4") (pinfunction "-IN_4") (pintype "passive"))
    )
  )
)
